# PGA.net
KiCad netlist of a schematic drawn in Altium Designer
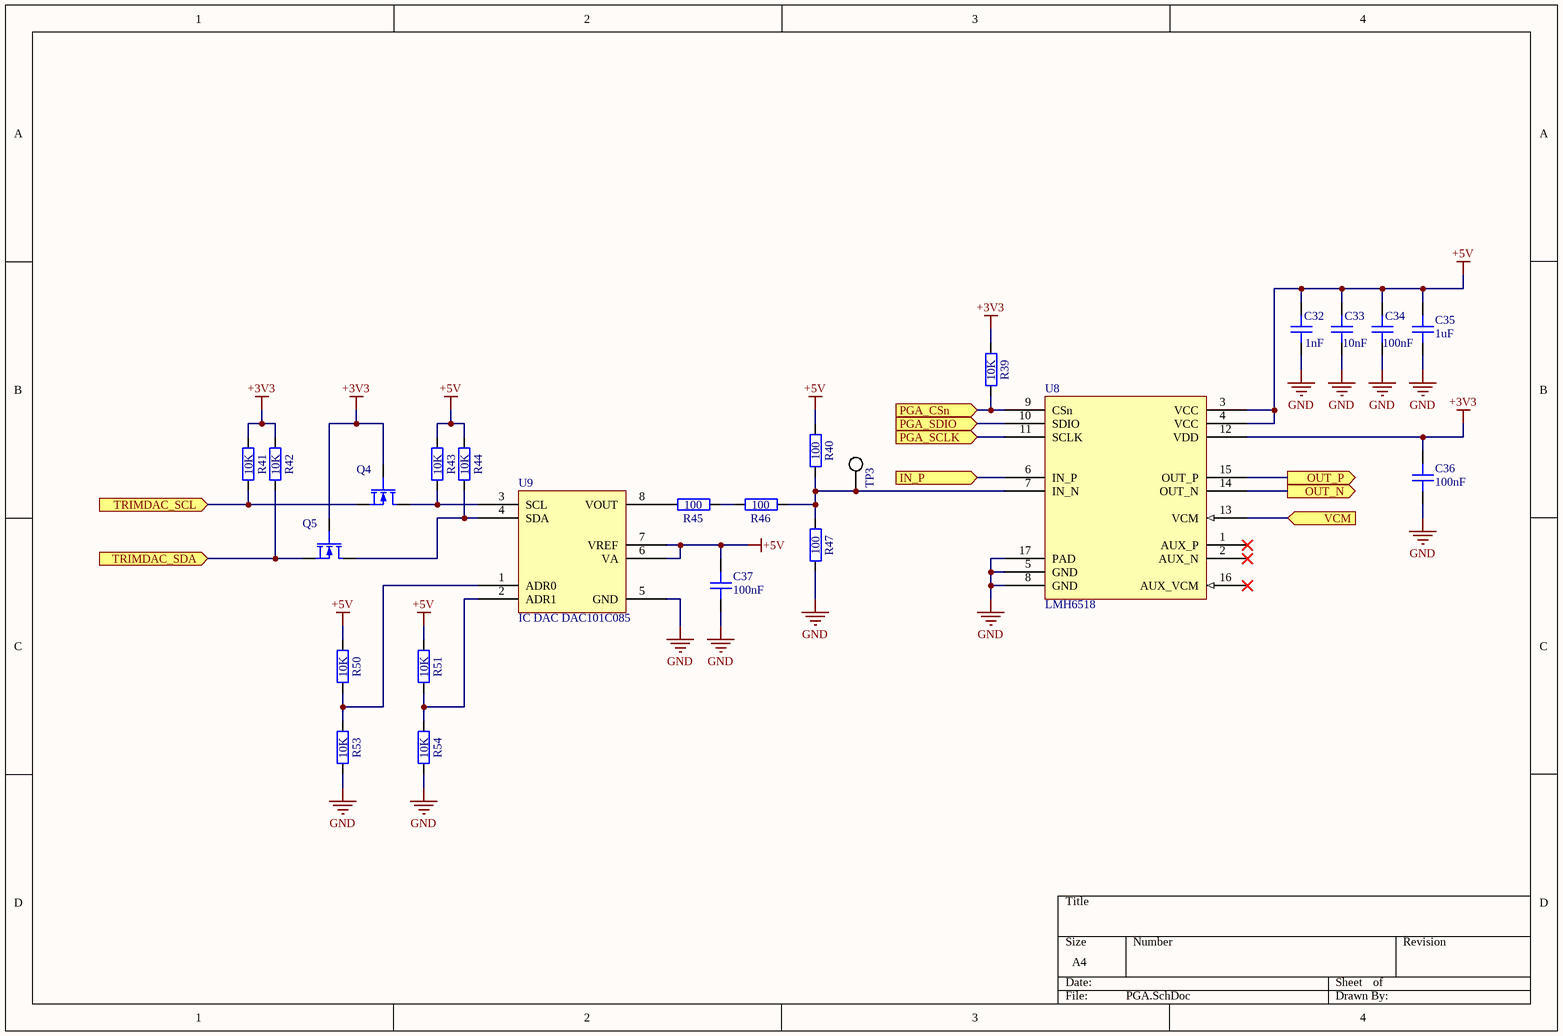
[diagram p0: PGA.SchDoc]

(export (version "E")
  (design (tool "Eeschema 10.0.6"))
  (components
    (comp (ref "C32")
      (value "1nF")
      (footprint "GEN_C_0402")
      (fields (field (name "Comment") "CAP 1nF 50V X7R 0402"))
      (libsource (lib "DSO") (part "CAP 1nF 50V X7R 0402"))
    )
    (comp (ref "C33")
      (value "10nF")
      (footprint "GEN_C_0402")
      (fields (field (name "Comment") "CAP 10nF 50V X7R 0402"))
      (libsource (lib "DSO") (part "CAP 10nF 50V X7R 0402"))
    )
    (comp (ref "C34")
      (value "100nF")
      (footprint "GEN_C_0402")
      (fields (field (name "Comment") "CAP 100nF 16V X7R 0402"))
      (libsource (lib "DSO") (part "CAP 100nF 16V X7R 0402"))
    )
    (comp (ref "C35")
      (value "1uF")
      (footprint "GEN_C_0402")
      (fields (field (name "Comment") "CAP 1uF 25V X5R 0402"))
      (libsource (lib "DSO") (part "CAP 1uF 25V X5R 0402"))
    )
    (comp (ref "C36")
      (value "100nF")
      (footprint "GEN_C_0402")
      (fields (field (name "Comment") "CAP 100nF 16V X7R 0402"))
      (libsource (lib "DSO") (part "CAP 100nF 16V X7R 0402"))
    )
    (comp (ref "C37")
      (value "100nF")
      (footprint "GEN_C_0402")
      (fields (field (name "Comment") "CAP 100nF 16V X7R 0402"))
      (libsource (lib "DSO") (part "CAP 100nF 16V X7R 0402"))
    )
    (comp (ref "Q4")
      (value "NMOS DMN62D0UW")
      (footprint "GEN_SOT_323")
      (libsource (lib "DSO") (part "NMOS DMN62D0UW"))
    )
    (comp (ref "Q5")
      (value "NMOS DMN62D0UW")
      (footprint "GEN_SOT_323")
      (libsource (lib "DSO") (part "NMOS DMN62D0UW"))
    )
    (comp (ref "R39")
      (value "10K")
      (footprint "GEN_R_0402")
      (fields (field (name "TOLERANCE") "1%") (field (name "Comment") "RES 10K OHM 1% 1/10W 0402"))
      (libsource (lib "") (part "RES 10K OHM 1% 1/10W 0402_1"))
    )
    (comp (ref "R40")
      (value "100")
      (footprint "GEN_R_0402")
      (fields (field (name "TOLERANCE") "1%") (field (name "Comment") "RES 100 OHM 1% 1/10W 0402"))
      (libsource (lib "DSO") (part "RES 100 OHM 1% 1/10W 0402"))
    )
    (comp (ref "R41")
      (value "10K")
      (footprint "GEN_R_0402")
      (fields (field (name "TOLERANCE") "1%") (field (name "Comment") "RES 10K OHM 1% 1/10W 0402"))
      (libsource (lib "DSO") (part "RES 10K OHM 1% 1/10W 0402"))
    )
    (comp (ref "R42")
      (value "10K")
      (footprint "GEN_R_0402")
      (fields (field (name "TOLERANCE") "1%") (field (name "Comment") "RES 10K OHM 1% 1/10W 0402"))
      (libsource (lib "DSO") (part "RES 10K OHM 1% 1/10W 0402"))
    )
    (comp (ref "R43")
      (value "10K")
      (footprint "GEN_R_0402")
      (fields (field (name "TOLERANCE") "1%") (field (name "Comment") "RES 10K OHM 1% 1/10W 0402"))
      (libsource (lib "DSO") (part "RES 10K OHM 1% 1/10W 0402"))
    )
    (comp (ref "R44")
      (value "10K")
      (footprint "GEN_R_0402")
      (fields (field (name "TOLERANCE") "1%") (field (name "Comment") "RES 10K OHM 1% 1/10W 0402"))
      (libsource (lib "DSO") (part "RES 10K OHM 1% 1/10W 0402"))
    )
    (comp (ref "R45")
      (value "100")
      (footprint "GEN_R_0402")
      (fields (field (name "TOLERANCE") "1%") (field (name "Comment") "RES 100 OHM 1% 1/10W 0402"))
      (libsource (lib "") (part "RES 100 OHM 1% 1/10W 0402_1"))
    )
    (comp (ref "R46")
      (value "100")
      (footprint "GEN_R_0402")
      (fields (field (name "TOLERANCE") "1%") (field (name "Comment") "RES 100 OHM 1% 1/10W 0402"))
      (libsource (lib "") (part "RES 100 OHM 1% 1/10W 0402_1"))
    )
    (comp (ref "R47")
      (value "100")
      (footprint "GEN_R_0402")
      (fields (field (name "TOLERANCE") "1%") (field (name "Comment") "RES 100 OHM 1% 1/10W 0402"))
      (libsource (lib "DSO") (part "RES 100 OHM 1% 1/10W 0402"))
    )
    (comp (ref "R50")
      (value "10K")
      (footprint "GEN_R_0402")
      (fields (field (name "TOLERANCE") "1%") (field (name "Comment") "RES 10K OHM 1% 1/10W 0402"))
      (libsource (lib "DSO") (part "RES 10K OHM 1% 1/10W 0402"))
    )
    (comp (ref "R51")
      (value "10K")
      (footprint "GEN_R_0402")
      (fields (field (name "TOLERANCE") "1%") (field (name "Comment") "RES 10K OHM 1% 1/10W 0402"))
      (libsource (lib "DSO") (part "RES 10K OHM 1% 1/10W 0402"))
    )
    (comp (ref "R53")
      (value "10K")
      (footprint "GEN_R_0402")
      (fields (field (name "TOLERANCE") "1%") (field (name "Comment") "RES 10K OHM 1% 1/10W 0402"))
      (libsource (lib "DSO") (part "RES 10K OHM 1% 1/10W 0402"))
    )
    (comp (ref "R54")
      (value "10K")
      (footprint "GEN_R_0402")
      (fields (field (name "TOLERANCE") "1%") (field (name "Comment") "RES 10K OHM 1% 1/10W 0402"))
      (libsource (lib "DSO") (part "RES 10K OHM 1% 1/10W 0402"))
    )
    (comp (ref "TP3") (value "5019") (footprint "KEY_5019") (libsource (lib "DSO") (part "TP KEYSTONE 5019")))
    (comp (ref "U8")
      (value "LMH6518")
      (footprint "TI_WQFN_RGH0016A")
      (libsource (lib "DSO") (part "IC PGA LMH6518"))
    )
    (comp (ref "U9")
      (value "IC DAC DAC101C085")
      (footprint "TI_VSSOP8_DGK")
      (libsource (lib "DSO") (part "IC DAC DAC101C085"))
    )
  )
  (nets
    (net (code "1") (name "+3V3") (class "Default")
      (node (ref "C36") (pin "2") (pinfunction "2_2") (pintype "passive"))
      (node (ref "Q4") (pin "2") (pinfunction "G_2") (pintype "passive"))
      (node (ref "Q5") (pin "2") (pinfunction "G_2") (pintype "passive"))
      (node (ref "R39") (pin "2") (pinfunction "2_2") (pintype "passive"))
      (node (ref "R41") (pin "2") (pinfunction "2_2") (pintype "passive"))
      (node (ref "R42") (pin "2") (pinfunction "2_2") (pintype "passive"))
      (node (ref "U8") (pin "12") (pinfunction "VDD_12") (pintype "power_in"))
    )
    (net (code "2") (name "+5V") (class "Default")
      (node (ref "C32") (pin "2") (pinfunction "2_2") (pintype "passive"))
      (node (ref "C33") (pin "2") (pinfunction "2_2") (pintype "passive"))
      (node (ref "C34") (pin "2") (pinfunction "2_2") (pintype "passive"))
      (node (ref "C35") (pin "2") (pinfunction "2_2") (pintype "passive"))
      (node (ref "C37") (pin "2") (pinfunction "2_2") (pintype "passive"))
      (node (ref "R40") (pin "2") (pinfunction "2_2") (pintype "passive"))
      (node (ref "R43") (pin "2") (pinfunction "2_2") (pintype "passive"))
      (node (ref "R44") (pin "2") (pinfunction "2_2") (pintype "passive"))
      (node (ref "R50") (pin "2") (pinfunction "2_2") (pintype "passive"))
      (node (ref "R51") (pin "2") (pinfunction "2_2") (pintype "passive"))
      (node (ref "U8") (pin "3") (pinfunction "VCC_3") (pintype "power_in"))
      (node (ref "U8") (pin "4") (pinfunction "VCC_4") (pintype "power_in"))
      (node (ref "U9") (pin "6") (pinfunction "VA_6") (pintype "power_in"))
      (node (ref "U9") (pin "7") (pinfunction "VREF_7") (pintype "power_in"))
    )
    (net (code "3") (name "/IN_P") (class "Default")
      (node (ref "U8") (pin "6") (pinfunction "IN_P_6") (pintype "passive"))
    )
    (net (code "4") (name "/OUT_N") (class "Default")
      (node (ref "U8") (pin "14") (pinfunction "OUT_N_14") (pintype "passive"))
    )
    (net (code "5") (name "/OUT_P") (class "Default")
      (node (ref "U8") (pin "15") (pinfunction "OUT_P_15") (pintype "passive"))
    )
    (net (code "6") (name "/PGA_CSn") (class "Default")
      (node (ref "R39") (pin "1") (pinfunction "1_1") (pintype "passive"))
      (node (ref "U8") (pin "9") (pinfunction "CSn_9") (pintype "passive"))
    )
    (net (code "7") (name "/PGA_SCLK") (class "Default")
      (node (ref "U8") (pin "11") (pinfunction "SCLK_11") (pintype "passive"))
    )
    (net (code "8") (name "/PGA_SDIO") (class "Default")
      (node (ref "U8") (pin "10") (pinfunction "SDIO_10") (pintype "passive"))
    )
    (net (code "9") (name "/TRIMDAC_SCL") (class "Default")
      (node (ref "Q4") (pin "3") (pinfunction "S_3") (pintype "passive"))
      (node (ref "R41") (pin "1") (pinfunction "1_1") (pintype "passive"))
    )
    (net (code "10") (name "/TRIMDAC_SDA") (class "Default")
      (node (ref "Q5") (pin "3") (pinfunction "S_3") (pintype "passive"))
      (node (ref "R42") (pin "1") (pinfunction "1_1") (pintype "passive"))
    )
    (net (code "11") (name "/VCM") (class "Default")
      (node (ref "U8") (pin "13") (pinfunction "VCM_13") (pintype "input"))
    )
    (net (code "12") (name "GND") (class "Default")
      (node (ref "C32") (pin "1") (pinfunction "1_1") (pintype "passive"))
      (node (ref "C33") (pin "1") (pinfunction "1_1") (pintype "passive"))
      (node (ref "C34") (pin "1") (pinfunction "1_1") (pintype "passive"))
      (node (ref "C35") (pin "1") (pinfunction "1_1") (pintype "passive"))
      (node (ref "C36") (pin "1") (pinfunction "1_1") (pintype "passive"))
      (node (ref "C37") (pin "1") (pinfunction "1_1") (pintype "passive"))
      (node (ref "R47") (pin "1") (pinfunction "1_1") (pintype "passive"))
      (node (ref "R53") (pin "1") (pinfunction "1_1") (pintype "passive"))
      (node (ref "R54") (pin "1") (pinfunction "1_1") (pintype "passive"))
      (node (ref "U8") (pin "17") (pinfunction "PAD_17") (pintype "power_in"))
      (node (ref "U8") (pin "5") (pinfunction "GND_5") (pintype "power_in"))
      (node (ref "U8") (pin "8") (pinfunction "GND_8") (pintype "power_in"))
      (node (ref "U9") (pin "5") (pinfunction "GND_5") (pintype "power_in"))
    )
    (net (code "13") (name "Net-(Q4-D)") (class "Default")
      (node (ref "Q4") (pin "1") (pinfunction "D_1") (pintype "passive"))
      (node (ref "R43") (pin "1") (pinfunction "1_1") (pintype "passive"))
      (node (ref "U9") (pin "3") (pinfunction "SCL_3") (pintype "passive"))
    )
    (net (code "14") (name "Net-(Q5-D)") (class "Default")
      (node (ref "Q5") (pin "1") (pinfunction "D_1") (pintype "passive"))
      (node (ref "R44") (pin "1") (pinfunction "1_1") (pintype "passive"))
      (node (ref "U9") (pin "4") (pinfunction "SDA_4") (pintype "passive"))
    )
    (net (code "15") (name "Net-(R45-Pad1)") (class "Default")
      (node (ref "R45") (pin "1") (pinfunction "1_1") (pintype "passive"))
      (node (ref "R46") (pin "2") (pinfunction "2_2") (pintype "passive"))
    )
    (net (code "16") (name "Net-(U8-IN_N)") (class "Default")
      (node (ref "R40") (pin "1") (pinfunction "1_1") (pintype "passive"))
      (node (ref "R46") (pin "1") (pinfunction "1_1") (pintype "passive"))
      (node (ref "R47") (pin "2") (pinfunction "2_2") (pintype "passive"))
      (node (ref "TP3") (pin "1") (pinfunction "1_1") (pintype "passive"))
      (node (ref "U8") (pin "7") (pinfunction "IN_N_7") (pintype "passive"))
    )
    (net (code "17") (name "Net-(U9-ADR0)") (class "Default")
      (node (ref "R50") (pin "1") (pinfunction "1_1") (pintype "passive"))
      (node (ref "R53") (pin "2") (pinfunction "2_2") (pintype "passive"))
      (node (ref "U9") (pin "1") (pinfunction "ADR0_1") (pintype "passive"))
    )
    (net (code "18") (name "Net-(U9-ADR1)") (class "Default")
      (node (ref "R51") (pin "1") (pinfunction "1_1") (pintype "passive"))
      (node (ref "R54") (pin "2") (pinfunction "2_2") (pintype "passive"))
      (node (ref "U9") (pin "2") (pinfunction "ADR1_2") (pintype "passive"))
    )
    (net (code "19") (name "Net-(U9-VOUT)") (class "Default")
      (node (ref "R45") (pin "2") (pinfunction "2_2") (pintype "passive"))
      (node (ref "U9") (pin "8") (pinfunction "VOUT_8") (pintype "passive"))
    )
    (net (code "20") (name "unconnected-(U8-AUX_N-Pad2)") (class "Default")
      (node (ref "U8") (pin "2") (pinfunction "AUX_N_2") (pintype "passive+no_connect"))
    )
    (net (code "21") (name "unconnected-(U8-AUX_P-Pad1)") (class "Default")
      (node (ref "U8") (pin "1") (pinfunction "AUX_P_1") (pintype "passive+no_connect"))
    )
    (net (code "22") (name "unconnected-(U8-AUX_VCM-Pad16)") (class "Default")
      (node (ref "U8") (pin "16") (pinfunction "AUX_VCM_16") (pintype "input+no_connect"))
    )
  )
)
